# 07-XORStatusLed.net
KiCad netlist of a schematic drawn in Altium Designer
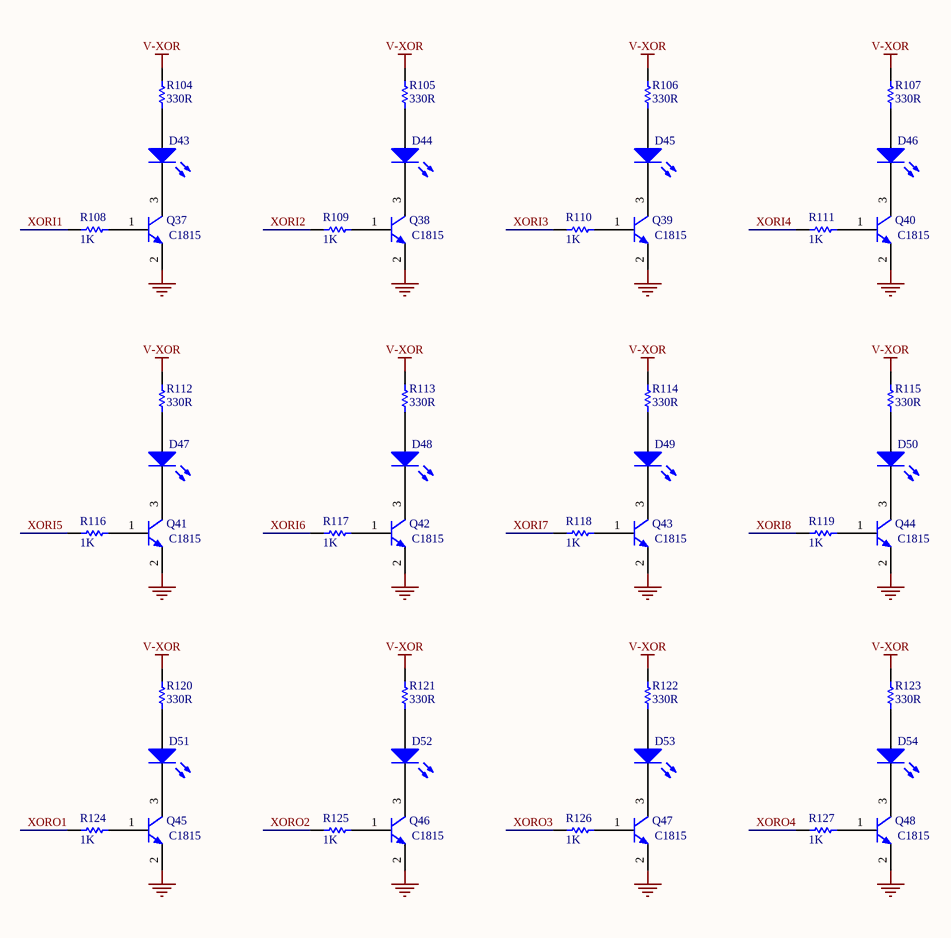
[diagram p0: 07-XORStatusLed.SchDoc]

(export (version "E")
  (design (tool "Eeschema 10.0.6"))
  (components
    (comp (ref "D43")
      (value "LED")
      (footprint "LED-3528")
      (description "Typical RED, GREEN, YELLOW, AMBER GaAs LED")
      (fields (field (name "PUBLISHER") "Altium Limited"))
      (libsource (lib "Miscellaneous Devices") (part "LED2"))
    )
    (comp (ref "D44")
      (value "LED")
      (footprint "LED-3528")
      (description "Typical RED, GREEN, YELLOW, AMBER GaAs LED")
      (fields (field (name "PUBLISHER") "Altium Limited"))
      (libsource (lib "Miscellaneous Devices") (part "LED2"))
    )
    (comp (ref "D45")
      (value "LED")
      (footprint "LED-3528")
      (description "Typical RED, GREEN, YELLOW, AMBER GaAs LED")
      (fields (field (name "PUBLISHER") "Altium Limited"))
      (libsource (lib "Miscellaneous Devices") (part "LED2"))
    )
    (comp (ref "D46")
      (value "LED")
      (footprint "LED-3528")
      (description "Typical RED, GREEN, YELLOW, AMBER GaAs LED")
      (fields (field (name "PUBLISHER") "Altium Limited"))
      (libsource (lib "Miscellaneous Devices") (part "LED2"))
    )
    (comp (ref "D47")
      (value "LED")
      (footprint "LED-3528")
      (description "Typical RED, GREEN, YELLOW, AMBER GaAs LED")
      (fields (field (name "PUBLISHER") "Altium Limited"))
      (libsource (lib "Miscellaneous Devices") (part "LED2"))
    )
    (comp (ref "D48")
      (value "LED")
      (footprint "LED-3528")
      (description "Typical RED, GREEN, YELLOW, AMBER GaAs LED")
      (fields (field (name "PUBLISHER") "Altium Limited"))
      (libsource (lib "Miscellaneous Devices") (part "LED2"))
    )
    (comp (ref "D49")
      (value "LED")
      (footprint "LED-3528")
      (description "Typical RED, GREEN, YELLOW, AMBER GaAs LED")
      (fields (field (name "PUBLISHER") "Altium Limited"))
      (libsource (lib "Miscellaneous Devices") (part "LED2"))
    )
    (comp (ref "D50")
      (value "LED")
      (footprint "LED-3528")
      (description "Typical RED, GREEN, YELLOW, AMBER GaAs LED")
      (fields (field (name "PUBLISHER") "Altium Limited"))
      (libsource (lib "Miscellaneous Devices") (part "LED2"))
    )
    (comp (ref "D51")
      (value "LED")
      (footprint "LED-3528")
      (description "Typical RED, GREEN, YELLOW, AMBER GaAs LED")
      (fields (field (name "PUBLISHER") "Altium Limited"))
      (libsource (lib "Miscellaneous Devices") (part "LED2"))
    )
    (comp (ref "D52")
      (value "LED")
      (footprint "LED-3528")
      (description "Typical RED, GREEN, YELLOW, AMBER GaAs LED")
      (fields (field (name "PUBLISHER") "Altium Limited"))
      (libsource (lib "Miscellaneous Devices") (part "LED2"))
    )
    (comp (ref "D53")
      (value "LED")
      (footprint "LED-3528")
      (description "Typical RED, GREEN, YELLOW, AMBER GaAs LED")
      (fields (field (name "PUBLISHER") "Altium Limited"))
      (libsource (lib "Miscellaneous Devices") (part "LED2"))
    )
    (comp (ref "D54")
      (value "LED")
      (footprint "LED-3528")
      (description "Typical RED, GREEN, YELLOW, AMBER GaAs LED")
      (fields (field (name "PUBLISHER") "Altium Limited"))
      (libsource (lib "Miscellaneous Devices") (part "LED2"))
    )
    (comp (ref "Q37")
      (value "C1815")
      (footprint "SOT23-321")
      (description "NPN Bipolar Transistor")
      (fields (field (name "Comment") "C1815-SMD"))
      (libsource (lib "Miscellaneous Devices") (part "NPN"))
    )
    (comp (ref "Q38")
      (value "C1815")
      (footprint "SOT23-321")
      (description "NPN Bipolar Transistor")
      (fields (field (name "Comment") "C1815-SMD"))
      (libsource (lib "Miscellaneous Devices") (part "NPN"))
    )
    (comp (ref "Q39")
      (value "C1815")
      (footprint "SOT23-321")
      (description "NPN Bipolar Transistor")
      (fields (field (name "Comment") "C1815-SMD"))
      (libsource (lib "Miscellaneous Devices") (part "NPN"))
    )
    (comp (ref "Q40")
      (value "C1815")
      (footprint "SOT23-321")
      (description "NPN Bipolar Transistor")
      (fields (field (name "Comment") "C1815-SMD"))
      (libsource (lib "Miscellaneous Devices") (part "NPN"))
    )
    (comp (ref "Q41")
      (value "C1815")
      (footprint "SOT23-321")
      (description "NPN Bipolar Transistor")
      (fields (field (name "Comment") "C1815-SMD"))
      (libsource (lib "Miscellaneous Devices") (part "NPN"))
    )
    (comp (ref "Q42")
      (value "C1815")
      (footprint "SOT23-321")
      (description "NPN Bipolar Transistor")
      (fields (field (name "Comment") "C1815-SMD"))
      (libsource (lib "Miscellaneous Devices") (part "NPN"))
    )
    (comp (ref "Q43")
      (value "C1815")
      (footprint "SOT23-321")
      (description "NPN Bipolar Transistor")
      (fields (field (name "Comment") "C1815-SMD"))
      (libsource (lib "Miscellaneous Devices") (part "NPN"))
    )
    (comp (ref "Q44")
      (value "C1815")
      (footprint "SOT23-321")
      (description "NPN Bipolar Transistor")
      (fields (field (name "Comment") "C1815-SMD"))
      (libsource (lib "Miscellaneous Devices") (part "NPN"))
    )
    (comp (ref "Q45")
      (value "C1815")
      (footprint "SOT23-321")
      (description "NPN Bipolar Transistor")
      (fields (field (name "Comment") "C1815-SMD"))
      (libsource (lib "Miscellaneous Devices") (part "NPN"))
    )
    (comp (ref "Q46")
      (value "C1815")
      (footprint "SOT23-321")
      (description "NPN Bipolar Transistor")
      (fields (field (name "Comment") "C1815-SMD"))
      (libsource (lib "Miscellaneous Devices") (part "NPN"))
    )
    (comp (ref "Q47")
      (value "C1815")
      (footprint "SOT23-321")
      (description "NPN Bipolar Transistor")
      (fields (field (name "Comment") "C1815-SMD"))
      (libsource (lib "Miscellaneous Devices") (part "NPN"))
    )
    (comp (ref "Q48")
      (value "C1815")
      (footprint "SOT23-321")
      (description "NPN Bipolar Transistor")
      (fields (field (name "Comment") "C1815-SMD"))
      (libsource (lib "Miscellaneous Devices") (part "NPN"))
    )
    (comp (ref "R104")
      (value "330R")
      (footprint "R-0805")
      (description "Resistor")
      (fields (field (name "PUBLISHER") "Altium Limited"))
      (libsource (lib "Miscellaneous Devices") (part "Res1"))
    )
    (comp (ref "R105")
      (value "330R")
      (footprint "R-0805")
      (description "Resistor")
      (fields (field (name "PUBLISHER") "Altium Limited"))
      (libsource (lib "Miscellaneous Devices") (part "Res1"))
    )
    (comp (ref "R106")
      (value "330R")
      (footprint "R-0805")
      (description "Resistor")
      (fields (field (name "PUBLISHER") "Altium Limited"))
      (libsource (lib "Miscellaneous Devices") (part "Res1"))
    )
    (comp (ref "R107")
      (value "330R")
      (footprint "R-0805")
      (description "Resistor")
      (fields (field (name "PUBLISHER") "Altium Limited"))
      (libsource (lib "Miscellaneous Devices") (part "Res1"))
    )
    (comp (ref "R108")
      (value "1K")
      (footprint "R-0805")
      (description "Resistor")
      (fields (field (name "PUBLISHER") "Altium Limited"))
      (libsource (lib "Miscellaneous Devices") (part "Res1"))
    )
    (comp (ref "R109")
      (value "1K")
      (footprint "R-0805")
      (description "Resistor")
      (fields (field (name "PUBLISHER") "Altium Limited"))
      (libsource (lib "Miscellaneous Devices") (part "Res1"))
    )
    (comp (ref "R110")
      (value "1K")
      (footprint "R-0805")
      (description "Resistor")
      (fields (field (name "PUBLISHER") "Altium Limited"))
      (libsource (lib "Miscellaneous Devices") (part "Res1"))
    )
    (comp (ref "R111")
      (value "1K")
      (footprint "R-0805")
      (description "Resistor")
      (fields (field (name "PUBLISHER") "Altium Limited"))
      (libsource (lib "Miscellaneous Devices") (part "Res1"))
    )
    (comp (ref "R112")
      (value "330R")
      (footprint "R-0805")
      (description "Resistor")
      (fields (field (name "PUBLISHER") "Altium Limited"))
      (libsource (lib "Miscellaneous Devices") (part "Res1"))
    )
    (comp (ref "R113")
      (value "330R")
      (footprint "R-0805")
      (description "Resistor")
      (fields (field (name "PUBLISHER") "Altium Limited"))
      (libsource (lib "Miscellaneous Devices") (part "Res1"))
    )
    (comp (ref "R114")
      (value "330R")
      (footprint "R-0805")
      (description "Resistor")
      (fields (field (name "PUBLISHER") "Altium Limited"))
      (libsource (lib "Miscellaneous Devices") (part "Res1"))
    )
    (comp (ref "R115")
      (value "330R")
      (footprint "R-0805")
      (description "Resistor")
      (fields (field (name "PUBLISHER") "Altium Limited"))
      (libsource (lib "Miscellaneous Devices") (part "Res1"))
    )
    (comp (ref "R116")
      (value "1K")
      (footprint "R-0805")
      (description "Resistor")
      (fields (field (name "PUBLISHER") "Altium Limited"))
      (libsource (lib "Miscellaneous Devices") (part "Res1"))
    )
    (comp (ref "R117")
      (value "1K")
      (footprint "R-0805")
      (description "Resistor")
      (fields (field (name "PUBLISHER") "Altium Limited"))
      (libsource (lib "Miscellaneous Devices") (part "Res1"))
    )
    (comp (ref "R118")
      (value "1K")
      (footprint "R-0805")
      (description "Resistor")
      (fields (field (name "PUBLISHER") "Altium Limited"))
      (libsource (lib "Miscellaneous Devices") (part "Res1"))
    )
    (comp (ref "R119")
      (value "1K")
      (footprint "R-0805")
      (description "Resistor")
      (fields (field (name "PUBLISHER") "Altium Limited"))
      (libsource (lib "Miscellaneous Devices") (part "Res1"))
    )
    (comp (ref "R120")
      (value "330R")
      (footprint "R-0805")
      (description "Resistor")
      (fields (field (name "PUBLISHER") "Altium Limited"))
      (libsource (lib "Miscellaneous Devices") (part "Res1"))
    )
    (comp (ref "R121")
      (value "330R")
      (footprint "R-0805")
      (description "Resistor")
      (fields (field (name "PUBLISHER") "Altium Limited"))
      (libsource (lib "Miscellaneous Devices") (part "Res1"))
    )
    (comp (ref "R122")
      (value "330R")
      (footprint "R-0805")
      (description "Resistor")
      (fields (field (name "PUBLISHER") "Altium Limited"))
      (libsource (lib "Miscellaneous Devices") (part "Res1"))
    )
    (comp (ref "R123")
      (value "330R")
      (footprint "R-0805")
      (description "Resistor")
      (fields (field (name "PUBLISHER") "Altium Limited"))
      (libsource (lib "Miscellaneous Devices") (part "Res1"))
    )
    (comp (ref "R124")
      (value "1K")
      (footprint "R-0805")
      (description "Resistor")
      (fields (field (name "PUBLISHER") "Altium Limited"))
      (libsource (lib "Miscellaneous Devices") (part "Res1"))
    )
    (comp (ref "R125")
      (value "1K")
      (footprint "R-0805")
      (description "Resistor")
      (fields (field (name "PUBLISHER") "Altium Limited"))
      (libsource (lib "Miscellaneous Devices") (part "Res1"))
    )
    (comp (ref "R126")
      (value "1K")
      (footprint "R-0805")
      (description "Resistor")
      (fields (field (name "PUBLISHER") "Altium Limited"))
      (libsource (lib "Miscellaneous Devices") (part "Res1"))
    )
    (comp (ref "R127")
      (value "1K")
      (footprint "R-0805")
      (description "Resistor")
      (fields (field (name "PUBLISHER") "Altium Limited"))
      (libsource (lib "Miscellaneous Devices") (part "Res1"))
    )
  )
  (nets
    (net (code "1") (name "/XORI1") (class "Default")
      (node (ref "R108") (pin "2") (pinfunction "2_2") (pintype "passive"))
    )
    (net (code "2") (name "/XORI2") (class "Default")
      (node (ref "R109") (pin "2") (pinfunction "2_2") (pintype "passive"))
    )
    (net (code "3") (name "/XORI3") (class "Default")
      (node (ref "R110") (pin "2") (pinfunction "2_2") (pintype "passive"))
    )
    (net (code "4") (name "/XORI4") (class "Default")
      (node (ref "R111") (pin "2") (pinfunction "2_2") (pintype "passive"))
    )
    (net (code "5") (name "/XORI5") (class "Default")
      (node (ref "R116") (pin "2") (pinfunction "2_2") (pintype "passive"))
    )
    (net (code "6") (name "/XORI6") (class "Default")
      (node (ref "R117") (pin "2") (pinfunction "2_2") (pintype "passive"))
    )
    (net (code "7") (name "/XORI7") (class "Default")
      (node (ref "R118") (pin "2") (pinfunction "2_2") (pintype "passive"))
    )
    (net (code "8") (name "/XORI8") (class "Default")
      (node (ref "R119") (pin "2") (pinfunction "2_2") (pintype "passive"))
    )
    (net (code "9") (name "/XORO1") (class "Default")
      (node (ref "R124") (pin "2") (pinfunction "2_2") (pintype "passive"))
    )
    (net (code "10") (name "/XORO2") (class "Default")
      (node (ref "R125") (pin "2") (pinfunction "2_2") (pintype "passive"))
    )
    (net (code "11") (name "/XORO3") (class "Default")
      (node (ref "R126") (pin "2") (pinfunction "2_2") (pintype "passive"))
    )
    (net (code "12") (name "/XORO4") (class "Default")
      (node (ref "R127") (pin "2") (pinfunction "2_2") (pintype "passive"))
    )
    (net (code "13") (name "GND") (class "Default")
      (node (ref "Q37") (pin "2") (pinfunction "E_2") (pintype "passive"))
      (node (ref "Q38") (pin "2") (pinfunction "E_2") (pintype "passive"))
      (node (ref "Q39") (pin "2") (pinfunction "E_2") (pintype "passive"))
      (node (ref "Q40") (pin "2") (pinfunction "E_2") (pintype "passive"))
      (node (ref "Q41") (pin "2") (pinfunction "E_2") (pintype "passive"))
      (node (ref "Q42") (pin "2") (pinfunction "E_2") (pintype "passive"))
      (node (ref "Q43") (pin "2") (pinfunction "E_2") (pintype "passive"))
      (node (ref "Q44") (pin "2") (pinfunction "E_2") (pintype "passive"))
      (node (ref "Q45") (pin "2") (pinfunction "E_2") (pintype "passive"))
      (node (ref "Q46") (pin "2") (pinfunction "E_2") (pintype "passive"))
      (node (ref "Q47") (pin "2") (pinfunction "E_2") (pintype "passive"))
      (node (ref "Q48") (pin "2") (pinfunction "E_2") (pintype "passive"))
    )
    (net (code "14") (name "Net-(D43-A)") (class "Default")
      (node (ref "D43") (pin "1") (pinfunction "A_1") (pintype "passive"))
      (node (ref "R104") (pin "1") (pinfunction "1_1") (pintype "passive"))
    )
    (net (code "15") (name "Net-(D43-K)") (class "Default")
      (node (ref "D43") (pin "2") (pinfunction "K_2") (pintype "passive"))
      (node (ref "Q37") (pin "3") (pinfunction "C_3") (pintype "passive"))
    )
    (net (code "16") (name "Net-(D44-A)") (class "Default")
      (node (ref "D44") (pin "1") (pinfunction "A_1") (pintype "passive"))
      (node (ref "R105") (pin "1") (pinfunction "1_1") (pintype "passive"))
    )
    (net (code "17") (name "Net-(D44-K)") (class "Default")
      (node (ref "D44") (pin "2") (pinfunction "K_2") (pintype "passive"))
      (node (ref "Q38") (pin "3") (pinfunction "C_3") (pintype "passive"))
    )
    (net (code "18") (name "Net-(D45-A)") (class "Default")
      (node (ref "D45") (pin "1") (pinfunction "A_1") (pintype "passive"))
      (node (ref "R106") (pin "1") (pinfunction "1_1") (pintype "passive"))
    )
    (net (code "19") (name "Net-(D45-K)") (class "Default")
      (node (ref "D45") (pin "2") (pinfunction "K_2") (pintype "passive"))
      (node (ref "Q39") (pin "3") (pinfunction "C_3") (pintype "passive"))
    )
    (net (code "20") (name "Net-(D46-A)") (class "Default")
      (node (ref "D46") (pin "1") (pinfunction "A_1") (pintype "passive"))
      (node (ref "R107") (pin "1") (pinfunction "1_1") (pintype "passive"))
    )
    (net (code "21") (name "Net-(D46-K)") (class "Default")
      (node (ref "D46") (pin "2") (pinfunction "K_2") (pintype "passive"))
      (node (ref "Q40") (pin "3") (pinfunction "C_3") (pintype "passive"))
    )
    (net (code "22") (name "Net-(D47-A)") (class "Default")
      (node (ref "D47") (pin "1") (pinfunction "A_1") (pintype "passive"))
      (node (ref "R112") (pin "1") (pinfunction "1_1") (pintype "passive"))
    )
    (net (code "23") (name "Net-(D47-K)") (class "Default")
      (node (ref "D47") (pin "2") (pinfunction "K_2") (pintype "passive"))
      (node (ref "Q41") (pin "3") (pinfunction "C_3") (pintype "passive"))
    )
    (net (code "24") (name "Net-(D48-A)") (class "Default")
      (node (ref "D48") (pin "1") (pinfunction "A_1") (pintype "passive"))
      (node (ref "R113") (pin "1") (pinfunction "1_1") (pintype "passive"))
    )
    (net (code "25") (name "Net-(D48-K)") (class "Default")
      (node (ref "D48") (pin "2") (pinfunction "K_2") (pintype "passive"))
      (node (ref "Q42") (pin "3") (pinfunction "C_3") (pintype "passive"))
    )
    (net (code "26") (name "Net-(D49-A)") (class "Default")
      (node (ref "D49") (pin "1") (pinfunction "A_1") (pintype "passive"))
      (node (ref "R114") (pin "1") (pinfunction "1_1") (pintype "passive"))
    )
    (net (code "27") (name "Net-(D49-K)") (class "Default")
      (node (ref "D49") (pin "2") (pinfunction "K_2") (pintype "passive"))
      (node (ref "Q43") (pin "3") (pinfunction "C_3") (pintype "passive"))
    )
    (net (code "28") (name "Net-(D50-A)") (class "Default")
      (node (ref "D50") (pin "1") (pinfunction "A_1") (pintype "passive"))
      (node (ref "R115") (pin "1") (pinfunction "1_1") (pintype "passive"))
    )
    (net (code "29") (name "Net-(D50-K)") (class "Default")
      (node (ref "D50") (pin "2") (pinfunction "K_2") (pintype "passive"))
      (node (ref "Q44") (pin "3") (pinfunction "C_3") (pintype "passive"))
    )
    (net (code "30") (name "Net-(D51-A)") (class "Default")
      (node (ref "D51") (pin "1") (pinfunction "A_1") (pintype "passive"))
      (node (ref "R120") (pin "1") (pinfunction "1_1") (pintype "passive"))
    )
    (net (code "31") (name "Net-(D51-K)") (class "Default")
      (node (ref "D51") (pin "2") (pinfunction "K_2") (pintype "passive"))
      (node (ref "Q45") (pin "3") (pinfunction "C_3") (pintype "passive"))
    )
    (net (code "32") (name "Net-(D52-A)") (class "Default")
      (node (ref "D52") (pin "1") (pinfunction "A_1") (pintype "passive"))
      (node (ref "R121") (pin "1") (pinfunction "1_1") (pintype "passive"))
    )
    (net (code "33") (name "Net-(D52-K)") (class "Default")
      (node (ref "D52") (pin "2") (pinfunction "K_2") (pintype "passive"))
      (node (ref "Q46") (pin "3") (pinfunction "C_3") (pintype "passive"))
    )
    (net (code "34") (name "Net-(D53-A)") (class "Default")
      (node (ref "D53") (pin "1") (pinfunction "A_1") (pintype "passive"))
      (node (ref "R122") (pin "1") (pinfunction "1_1") (pintype "passive"))
    )
    (net (code "35") (name "Net-(D53-K)") (class "Default")
      (node (ref "D53") (pin "2") (pinfunction "K_2") (pintype "passive"))
      (node (ref "Q47") (pin "3") (pinfunction "C_3") (pintype "passive"))
    )
    (net (code "36") (name "Net-(D54-A)") (class "Default")
      (node (ref "D54") (pin "1") (pinfunction "A_1") (pintype "passive"))
      (node (ref "R123") (pin "1") (pinfunction "1_1") (pintype "passive"))
    )
    (net (code "37") (name "Net-(D54-K)") (class "Default")
      (node (ref "D54") (pin "2") (pinfunction "K_2") (pintype "passive"))
      (node (ref "Q48") (pin "3") (pinfunction "C_3") (pintype "passive"))
    )
    (net (code "38") (name "Net-(Q37-B)") (class "Default")
      (node (ref "Q37") (pin "1") (pinfunction "B_1") (pintype "passive"))
      (node (ref "R108") (pin "1") (pinfunction "1_1") (pintype "passive"))
    )
    (net (code "39") (name "Net-(Q38-B)") (class "Default")
      (node (ref "Q38") (pin "1") (pinfunction "B_1") (pintype "passive"))
      (node (ref "R109") (pin "1") (pinfunction "1_1") (pintype "passive"))
    )
    (net (code "40") (name "Net-(Q39-B)") (class "Default")
      (node (ref "Q39") (pin "1") (pinfunction "B_1") (pintype "passive"))
      (node (ref "R110") (pin "1") (pinfunction "1_1") (pintype "passive"))
    )
    (net (code "41") (name "Net-(Q40-B)") (class "Default")
      (node (ref "Q40") (pin "1") (pinfunction "B_1") (pintype "passive"))
      (node (ref "R111") (pin "1") (pinfunction "1_1") (pintype "passive"))
    )
    (net (code "42") (name "Net-(Q41-B)") (class "Default")
      (node (ref "Q41") (pin "1") (pinfunction "B_1") (pintype "passive"))
      (node (ref "R116") (pin "1") (pinfunction "1_1") (pintype "passive"))
    )
    (net (code "43") (name "Net-(Q42-B)") (class "Default")
      (node (ref "Q42") (pin "1") (pinfunction "B_1") (pintype "passive"))
      (node (ref "R117") (pin "1") (pinfunction "1_1") (pintype "passive"))
    )
    (net (code "44") (name "Net-(Q43-B)") (class "Default")
      (node (ref "Q43") (pin "1") (pinfunction "B_1") (pintype "passive"))
      (node (ref "R118") (pin "1") (pinfunction "1_1") (pintype "passive"))
    )
    (net (code "45") (name "Net-(Q44-B)") (class "Default")
      (node (ref "Q44") (pin "1") (pinfunction "B_1") (pintype "passive"))
      (node (ref "R119") (pin "1") (pinfunction "1_1") (pintype "passive"))
    )
    (net (code "46") (name "Net-(Q45-B)") (class "Default")
      (node (ref "Q45") (pin "1") (pinfunction "B_1") (pintype "passive"))
      (node (ref "R124") (pin "1") (pinfunction "1_1") (pintype "passive"))
    )
    (net (code "47") (name "Net-(Q46-B)") (class "Default")
      (node (ref "Q46") (pin "1") (pinfunction "B_1") (pintype "passive"))
      (node (ref "R125") (pin "1") (pinfunction "1_1") (pintype "passive"))
    )
    (net (code "48") (name "Net-(Q47-B)") (class "Default")
      (node (ref "Q47") (pin "1") (pinfunction "B_1") (pintype "passive"))
      (node (ref "R126") (pin "1") (pinfunction "1_1") (pintype "passive"))
    )
    (net (code "49") (name "Net-(Q48-B)") (class "Default")
      (node (ref "Q48") (pin "1") (pinfunction "B_1") (pintype "passive"))
      (node (ref "R127") (pin "1") (pinfunction "1_1") (pintype "passive"))
    )
    (net (code "50") (name "V-XOR") (class "Default")
      (node (ref "R104") (pin "2") (pinfunction "2_2") (pintype "passive"))
      (node (ref "R105") (pin "2") (pinfunction "2_2") (pintype "passive"))
      (node (ref "R106") (pin "2") (pinfunction "2_2") (pintype "passive"))
      (node (ref "R107") (pin "2") (pinfunction "2_2") (pintype "passive"))
      (node (ref "R112") (pin "2") (pinfunction "2_2") (pintype "passive"))
      (node (ref "R113") (pin "2") (pinfunction "2_2") (pintype "passive"))
      (node (ref "R114") (pin "2") (pinfunction "2_2") (pintype "passive"))
      (node (ref "R115") (pin "2") (pinfunction "2_2") (pintype "passive"))
      (node (ref "R120") (pin "2") (pinfunction "2_2") (pintype "passive"))
      (node (ref "R121") (pin "2") (pinfunction "2_2") (pintype "passive"))
      (node (ref "R122") (pin "2") (pinfunction "2_2") (pintype "passive"))
      (node (ref "R123") (pin "2") (pinfunction "2_2") (pintype "passive"))
    )
  )
)
